# VS1005BOB-Pico-LCD_2024-02-10.net
KiCad netlist of a schematic drawn in Altium Designer
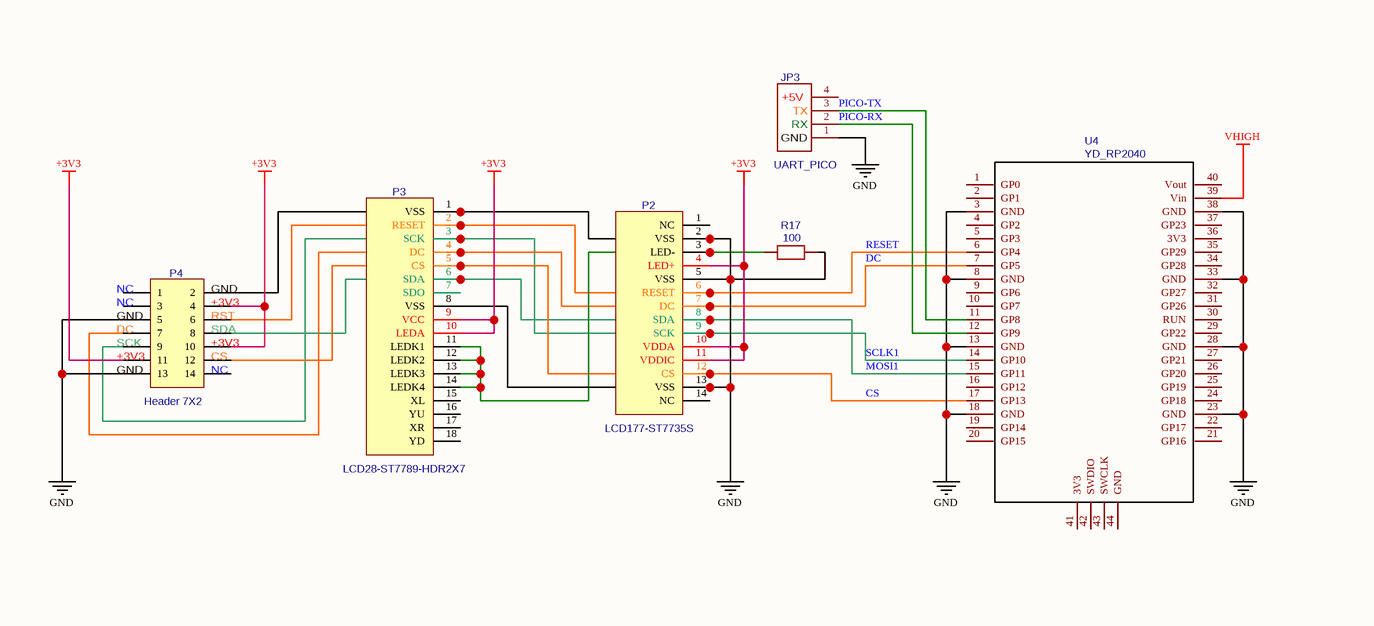
[diagram p0: VS1005BOB-Pico-LCD_2024-02-10.schdoc, left]
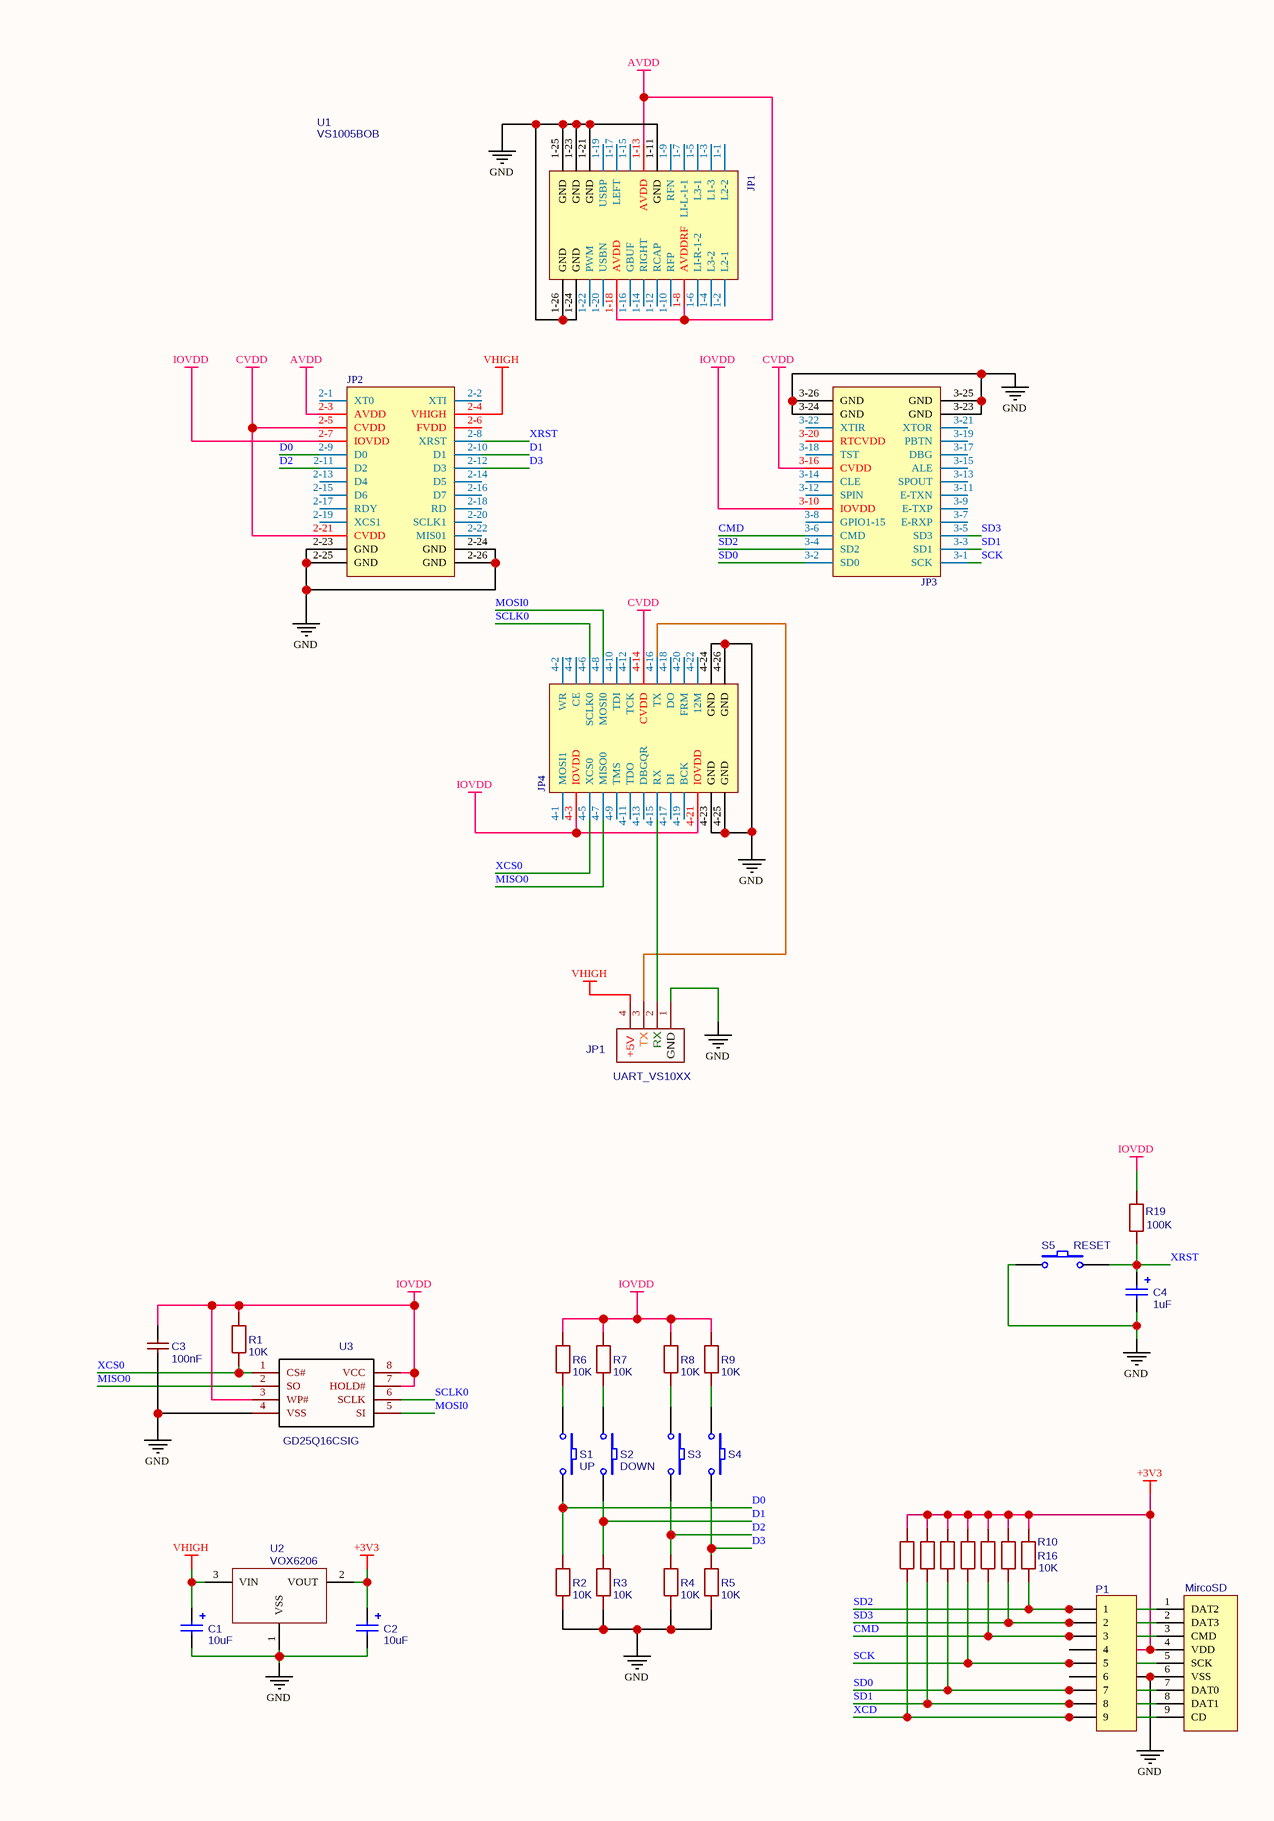
[diagram p1: VS1005BOB-Pico-LCD_2024-02-10.schdoc, right]

(export (version "E")
  (design (tool "Eeschema 10.0.6"))
  (components
    (comp (ref "C1")
      (value "10uF")
      (fields (field (name "PUBLISHER") "Altium Limited") (field (name "CONTRIBUTOR") "kmok163"))
      (libsource (lib "altium-import") (part "root_0_10uF_"))
    )
    (comp (ref "C2")
      (value "10uF")
      (fields (field (name "PUBLISHER") "Altium Limited") (field (name "CONTRIBUTOR") "kmok163"))
      (libsource (lib "altium-import") (part "root_0_10uF_"))
    )
    (comp (ref "C3")
      (value "100nF")
      (fields
        (field (name "MANUFACTURER PART") "CC0805KRX7R9BB104")
        (field (name "MANUFACTURER") "YAGEO")
        (field (name "CONTRIBUTOR") "fen-1")
      )
      (libsource (lib "altium-import") (part "root_3_100nF_"))
    )
    (comp (ref "C4")
      (value "1uF")
      (fields (field (name "PUBLISHER") "Altium Limited") (field (name "CONTRIBUTOR") "kmok163"))
      (libsource (lib "altium-import") (part "root_0_1uF_"))
    )
    (comp (ref "JP1")
      (value "UART_VS10XX")
      (description "Header 4")
      (fields (field (name "CONTRIBUTOR") "SparkFun"))
      (libsource (lib "altium-import") (part "root_1_UART_VS10XX_"))
    )
    (comp (ref "JP3")
      (value "UART_PICO")
      (description "Header 4")
      (fields (field (name "CONTRIBUTOR") "SparkFun"))
      (libsource (lib "altium-import") (part "root_0_UART_PICO_"))
    )
    (comp (ref "P1")
      (value "Header 9")
      (fields (field (name "PUBLISHER") "Altium Limited") (field (name "CONTRIBUTOR") "kmok163"))
      (libsource (lib "altium-import") (part "root_0_Header 9_"))
    )
    (comp (ref "P2")
      (value "LCD177-ST7735S")
      (fields (field (name "PUBLISHER") "Altium Limited") (field (name "CONTRIBUTOR") "kmok163"))
      (libsource (lib "altium-import") (part "root_0_LCD177-ST7735S_"))
    )
    (comp (ref "P3")
      (value "LCD28-ST7789-HDR2X7")
      (fields (field (name "PUBLISHER") "Altium Limited") (field (name "CONTRIBUTOR") "kmok163"))
      (libsource (lib "altium-import") (part "root_0_LCD28-ST7789-HDR2X7_"))
    )
    (comp (ref "P4")
      (value "Header 7X2")
      (fields (field (name "PUBLISHER") "Altium Limited") (field (name "CONTRIBUTOR") "lingtian"))
      (libsource (lib "altium-import") (part "root_0_Header 7X2_"))
    )
    (comp (ref "P6")
      (value "MircoSD")
      (fields (field (name "PUBLISHER") "Altium Limited") (field (name "CONTRIBUTOR") "kmok163"))
      (libsource (lib "altium-import") (part "root_0_MircoSD_"))
    )
    (comp (ref "R1")
      (value "10K")
      (fields (field (name "CONTRIBUTOR") "EDAUSER001"))
      (libsource (lib "altium-import") (part "root_1_10K_"))
    )
    (comp (ref "R2")
      (value "10K")
      (fields (field (name "CONTRIBUTOR") "EDAUSER001"))
      (libsource (lib "altium-import") (part "root_1_10K_"))
    )
    (comp (ref "R3")
      (value "10K")
      (fields (field (name "CONTRIBUTOR") "EDAUSER001"))
      (libsource (lib "altium-import") (part "root_1_10K_"))
    )
    (comp (ref "R4")
      (value "10K")
      (fields (field (name "CONTRIBUTOR") "EDAUSER001"))
      (libsource (lib "altium-import") (part "root_1_10K_"))
    )
    (comp (ref "R5")
      (value "10K")
      (fields (field (name "CONTRIBUTOR") "EDAUSER001"))
      (libsource (lib "altium-import") (part "root_1_10K_"))
    )
    (comp (ref "R6")
      (value "10K")
      (fields (field (name "CONTRIBUTOR") "EDAUSER001"))
      (libsource (lib "altium-import") (part "root_1_10K_"))
    )
    (comp (ref "R7")
      (value "10K")
      (fields (field (name "CONTRIBUTOR") "EDAUSER001"))
      (libsource (lib "altium-import") (part "root_1_10K_"))
    )
    (comp (ref "R8")
      (value "10K")
      (fields (field (name "CONTRIBUTOR") "EDAUSER001"))
      (libsource (lib "altium-import") (part "root_1_10K_"))
    )
    (comp (ref "R9")
      (value "10K")
      (fields (field (name "CONTRIBUTOR") "EDAUSER001"))
      (libsource (lib "altium-import") (part "root_1_10K_"))
    )
    (comp (ref "R10")
      (value "10K")
      (fields (field (name "CONTRIBUTOR") "EDAUSER001"))
      (libsource (lib "altium-import") (part "root_1_10K_"))
    )
    (comp (ref "R11")
      (value "10K")
      (fields (field (name "CONTRIBUTOR") "EDAUSER001"))
      (libsource (lib "altium-import") (part "root_1_10K_"))
    )
    (comp (ref "R12")
      (value "10K")
      (fields (field (name "CONTRIBUTOR") "EDAUSER001"))
      (libsource (lib "altium-import") (part "root_1_10K_"))
    )
    (comp (ref "R13")
      (value "10K")
      (fields (field (name "CONTRIBUTOR") "EDAUSER001"))
      (libsource (lib "altium-import") (part "root_1_10K_"))
    )
    (comp (ref "R14")
      (value "10K")
      (fields (field (name "CONTRIBUTOR") "EDAUSER001"))
      (libsource (lib "altium-import") (part "root_1_10K_"))
    )
    (comp (ref "R15")
      (value "10K")
      (fields (field (name "CONTRIBUTOR") "EDAUSER001"))
      (libsource (lib "altium-import") (part "root_1_10K_"))
    )
    (comp (ref "R16")
      (value "10K")
      (fields (field (name "CONTRIBUTOR") "EDAUSER001"))
      (libsource (lib "altium-import") (part "root_1_10K_"))
    )
    (comp (ref "R17")
      (value "100")
      (fields (field (name "CONTRIBUTOR") "EDAUSER001"))
      (libsource (lib "altium-import") (part "root_0_100_"))
    )
    (comp (ref "R19")
      (value "100K")
      (fields (field (name "CONTRIBUTOR") "EDAUSER001"))
      (libsource (lib "altium-import") (part "root_1_100K_"))
    )
    (comp (ref "S1")
      (value "UP")
      (fields (field (name "PUBLISHER") "Altium Limited") (field (name "CONTRIBUTOR") "kmok163"))
      (libsource (lib "altium-import") (part "root_3_UP_"))
    )
    (comp (ref "S2")
      (value "DOWN")
      (fields (field (name "PUBLISHER") "Altium Limited") (field (name "CONTRIBUTOR") "kmok163"))
      (libsource (lib "altium-import") (part "root_3_DOWN_"))
    )
    (comp (ref "S3")
      (value "D2")
      (fields (field (name "PUBLISHER") "Altium Limited") (field (name "CONTRIBUTOR") "kmok163"))
      (libsource (lib "altium-import") (part "root_3_D2_"))
    )
    (comp (ref "S4")
      (value "D3")
      (fields (field (name "PUBLISHER") "Altium Limited") (field (name "CONTRIBUTOR") "kmok163"))
      (libsource (lib "altium-import") (part "root_3_D3_"))
    )
    (comp (ref "S5")
      (value "RESET")
      (fields (field (name "PUBLISHER") "Altium Limited") (field (name "CONTRIBUTOR") "kmok163"))
      (libsource (lib "altium-import") (part "root_0_RESET_"))
    )
    (comp (ref "U1")
      (value "VS1005BOB")
      (fields (field (name "MANUFACTURER") "VLSI Solution Oy") (field (name "CONTRIBUTOR") "kmok163"))
      (libsource (lib "altium-import") (part "root_0_VS1005BOB_"))
    )
    (comp (ref "U2")
      (value "VOX6206")
      (fields (field (name "PUBLISHER") "Altium Limited") (field (name "CONTRIBUTOR") "kmok163"))
      (libsource (lib "altium-import") (part "root_0_VOX6206_"))
    )
    (comp (ref "U3")
      (value "GD25Q16CSIG")
      (fields (field (name "MANUFACTURER") "GigaDevice(兆易创新)"))
      (libsource (lib "altium-import") (part "root_0_GD25Q16CSIG_"))
    )
    (comp (ref "U4")
      (value "YD_RP2040")
      (fields (field (name "CONTRIBUTOR") "armxu"))
      (libsource (lib "altium-import") (part "root_0_YD_RP2040_"))
    )
  )
  (nets
    (net (code "1") (name "+3V3") (class "Default")
      (node (ref "C2") (pin "1") (pinfunction "1_1") (pintype "passive"))
      (node (ref "P1") (pin "4") (pinfunction "4_4") (pintype "passive"))
      (node (ref "P2") (pin "10") (pinfunction "VDDA_10") (pintype "passive"))
      (node (ref "P2") (pin "11") (pinfunction "VDDIC_11") (pintype "passive"))
      (node (ref "P2") (pin "4") (pinfunction "LED+_4") (pintype "passive"))
      (node (ref "P3") (pin "10") (pinfunction "LEDA_10") (pintype "passive"))
      (node (ref "P3") (pin "9") (pinfunction "VCC_9") (pintype "passive"))
      (node (ref "P4") (pin "10") (pinfunction "10_10") (pintype "passive"))
      (node (ref "P4") (pin "11") (pinfunction "11_11") (pintype "passive"))
      (node (ref "P4") (pin "4") (pinfunction "4_4") (pintype "passive"))
      (node (ref "P6") (pin "4") (pinfunction "VDD_4") (pintype "passive"))
      (node (ref "R10") (pin "2") (pinfunction "2_2") (pintype "passive"))
      (node (ref "R11") (pin "2") (pinfunction "2_2") (pintype "passive"))
      (node (ref "R12") (pin "2") (pinfunction "2_2") (pintype "passive"))
      (node (ref "R13") (pin "2") (pinfunction "2_2") (pintype "passive"))
      (node (ref "R14") (pin "2") (pinfunction "2_2") (pintype "passive"))
      (node (ref "R15") (pin "2") (pinfunction "2_2") (pintype "passive"))
      (node (ref "R16") (pin "2") (pinfunction "2_2") (pintype "passive"))
      (node (ref "U2") (pin "2") (pinfunction "VOUT_2") (pintype "passive"))
    )
    (net (code "2") (name "/CMD") (class "Default")
      (node (ref "P1") (pin "3") (pinfunction "3_3") (pintype "passive"))
      (node (ref "P6") (pin "3") (pinfunction "CMD_3") (pintype "passive"))
      (node (ref "R14") (pin "1") (pinfunction "1_1") (pintype "passive"))
      (node (ref "U1") (pin "3-6") (pinfunction "CMD_3-6") (pintype "passive"))
    )
    (net (code "3") (name "/CS") (class "Default")
      (node (ref "P2") (pin "12") (pinfunction "CS_12") (pintype "passive"))
      (node (ref "P3") (pin "5") (pinfunction "CS_5") (pintype "passive"))
      (node (ref "P4") (pin "12") (pinfunction "12_12") (pintype "passive"))
      (node (ref "U4") (pin "17") (pinfunction "GP13_17") (pintype "passive"))
    )
    (net (code "4") (name "/D0") (class "Default")
      (node (ref "R2") (pin "2") (pinfunction "2_2") (pintype "passive"))
      (node (ref "S1") (pin "2") (pinfunction "2_2") (pintype "passive"))
      (node (ref "U1") (pin "2-9") (pinfunction "D0_2-9") (pintype "passive"))
    )
    (net (code "5") (name "/D1") (class "Default")
      (node (ref "R3") (pin "2") (pinfunction "2_2") (pintype "passive"))
      (node (ref "S2") (pin "2") (pinfunction "2_2") (pintype "passive"))
      (node (ref "U1") (pin "2-10") (pinfunction "D1_2-10") (pintype "passive"))
    )
    (net (code "6") (name "/D2") (class "Default")
      (node (ref "R4") (pin "2") (pinfunction "2_2") (pintype "passive"))
      (node (ref "S3") (pin "2") (pinfunction "2_2") (pintype "passive"))
      (node (ref "U1") (pin "2-11") (pinfunction "D2_2-11") (pintype "passive"))
    )
    (net (code "7") (name "/D3") (class "Default")
      (node (ref "R5") (pin "2") (pinfunction "2_2") (pintype "passive"))
      (node (ref "S4") (pin "2") (pinfunction "2_2") (pintype "passive"))
      (node (ref "U1") (pin "2-12") (pinfunction "D3_2-12") (pintype "passive"))
    )
    (net (code "8") (name "/DC") (class "Default")
      (node (ref "P2") (pin "7") (pinfunction "DC_7") (pintype "passive"))
      (node (ref "P3") (pin "4") (pinfunction "DC_4") (pintype "passive"))
      (node (ref "P4") (pin "7") (pinfunction "7_7") (pintype "passive"))
      (node (ref "U4") (pin "7") (pinfunction "GP5_7") (pintype "passive"))
    )
    (net (code "9") (name "/MISO0") (class "Default")
      (node (ref "U1") (pin "4-7") (pinfunction "MISO0_4-7") (pintype "passive"))
      (node (ref "U3") (pin "2") (pinfunction "SO_2") (pintype "passive"))
    )
    (net (code "10") (name "/MOSI0") (class "Default")
      (node (ref "U1") (pin "4-8") (pinfunction "MOSI0_4-8") (pintype "passive"))
      (node (ref "U3") (pin "5") (pinfunction "SI_5") (pintype "passive"))
    )
    (net (code "11") (name "/MOSI1") (class "Default")
      (node (ref "P2") (pin "8") (pinfunction "SDA_8") (pintype "passive"))
      (node (ref "P3") (pin "6") (pinfunction "SDA_6") (pintype "passive"))
      (node (ref "P4") (pin "8") (pinfunction "8_8") (pintype "passive"))
      (node (ref "U4") (pin "15") (pinfunction "GP11_15") (pintype "passive"))
    )
    (net (code "12") (name "/PICO-RX") (class "Default")
      (node (ref "JP3") (pin "2") (pinfunction "2_2") (pintype "passive"))
      (node (ref "U4") (pin "12") (pinfunction "GP9_12") (pintype "passive"))
    )
    (net (code "13") (name "/PICO-TX") (class "Default")
      (node (ref "JP3") (pin "3") (pinfunction "3_3") (pintype "passive"))
      (node (ref "U4") (pin "11") (pinfunction "GP8_11") (pintype "passive"))
    )
    (net (code "14") (name "/RESET") (class "Default")
      (node (ref "P2") (pin "6") (pinfunction "RESET_6") (pintype "passive"))
      (node (ref "P3") (pin "2") (pinfunction "RESET_2") (pintype "passive"))
      (node (ref "P4") (pin "6") (pinfunction "6_6") (pintype "passive"))
      (node (ref "U4") (pin "6") (pinfunction "GP4_6") (pintype "passive"))
    )
    (net (code "15") (name "/SCK") (class "Default")
      (node (ref "P1") (pin "5") (pinfunction "5_5") (pintype "passive"))
      (node (ref "P6") (pin "5") (pinfunction "SCK_5") (pintype "passive"))
      (node (ref "R13") (pin "1") (pinfunction "1_1") (pintype "passive"))
      (node (ref "U1") (pin "3-1") (pinfunction "SCK_3-1") (pintype "passive"))
    )
    (net (code "16") (name "/SCLK0") (class "Default")
      (node (ref "U1") (pin "4-6") (pinfunction "SCLK0_4-6") (pintype "passive"))
      (node (ref "U3") (pin "6") (pinfunction "SCLK_6") (pintype "passive"))
    )
    (net (code "17") (name "/SCLK1") (class "Default")
      (node (ref "P2") (pin "9") (pinfunction "SCK_9") (pintype "passive"))
      (node (ref "P3") (pin "3") (pinfunction "SCK_3") (pintype "passive"))
      (node (ref "P4") (pin "9") (pinfunction "9_9") (pintype "passive"))
      (node (ref "U4") (pin "14") (pinfunction "GP10_14") (pintype "passive"))
    )
    (net (code "18") (name "/SD0") (class "Default")
      (node (ref "P1") (pin "7") (pinfunction "7_7") (pintype "passive"))
      (node (ref "P6") (pin "7") (pinfunction "DAT0_7") (pintype "passive"))
      (node (ref "R12") (pin "1") (pinfunction "1_1") (pintype "passive"))
      (node (ref "U1") (pin "3-2") (pinfunction "SD0_3-2") (pintype "passive"))
    )
    (net (code "19") (name "/SD1") (class "Default")
      (node (ref "P1") (pin "8") (pinfunction "8_8") (pintype "passive"))
      (node (ref "P6") (pin "8") (pinfunction "DAT1_8") (pintype "passive"))
      (node (ref "R11") (pin "1") (pinfunction "1_1") (pintype "passive"))
      (node (ref "U1") (pin "3-3") (pinfunction "SD1_3-3") (pintype "passive"))
    )
    (net (code "20") (name "/SD2") (class "Default")
      (node (ref "P1") (pin "1") (pinfunction "1_1") (pintype "passive"))
      (node (ref "P6") (pin "1") (pinfunction "DAT2_1") (pintype "passive"))
      (node (ref "R16") (pin "1") (pinfunction "1_1") (pintype "passive"))
      (node (ref "U1") (pin "3-4") (pinfunction "SD2_3-4") (pintype "passive"))
    )
    (net (code "21") (name "/SD3") (class "Default")
      (node (ref "P1") (pin "2") (pinfunction "2_2") (pintype "passive"))
      (node (ref "P6") (pin "2") (pinfunction "DAT3_2") (pintype "passive"))
      (node (ref "R15") (pin "1") (pinfunction "1_1") (pintype "passive"))
      (node (ref "U1") (pin "3-5") (pinfunction "SD3_3-5") (pintype "passive"))
    )
    (net (code "22") (name "/XCD") (class "Default")
      (node (ref "P1") (pin "9") (pinfunction "9_9") (pintype "passive"))
      (node (ref "P6") (pin "9") (pinfunction "CD_9") (pintype "passive"))
      (node (ref "R10") (pin "1") (pinfunction "1_1") (pintype "passive"))
    )
    (net (code "23") (name "/XCS0") (class "Default")
      (node (ref "R1") (pin "1") (pinfunction "1_1") (pintype "passive"))
      (node (ref "U1") (pin "4-5") (pinfunction "XCS0_4-5") (pintype "passive"))
      (node (ref "U3") (pin "1") (pinfunction "CS#_1") (pintype "passive"))
    )
    (net (code "24") (name "/XRST") (class "Default")
      (node (ref "C4") (pin "1") (pinfunction "1_1") (pintype "passive"))
      (node (ref "R19") (pin "1") (pinfunction "1_1") (pintype "passive"))
      (node (ref "S5") (pin "2") (pinfunction "2_2") (pintype "passive"))
      (node (ref "U1") (pin "2-8") (pinfunction "XRST_2-8") (pintype "passive"))
    )
    (net (code "25") (name "AVDD") (class "Default")
      (node (ref "U1") (pin "1-13") (pinfunction "AVDD_1-13") (pintype "passive"))
      (node (ref "U1") (pin "1-18") (pinfunction "AVDD_1-18") (pintype "passive"))
      (node (ref "U1") (pin "1-8") (pinfunction "AVDDRF_1-8") (pintype "passive"))
      (node (ref "U1") (pin "2-3") (pinfunction "AVDD_2-3") (pintype "passive"))
    )
    (net (code "26") (name "CVDD") (class "Default")
      (node (ref "U1") (pin "2-21") (pinfunction "CVDD_2-21") (pintype "passive"))
      (node (ref "U1") (pin "2-5") (pinfunction "CVDD_2-5") (pintype "passive"))
      (node (ref "U1") (pin "3-16") (pinfunction "CVDD_3-16") (pintype "passive"))
      (node (ref "U1") (pin "4-14") (pinfunction "CVDD_4-14") (pintype "passive"))
    )
    (net (code "27") (name "GND") (class "Default")
      (node (ref "C1") (pin "2") (pinfunction "2_2") (pintype "passive"))
      (node (ref "C2") (pin "2") (pinfunction "2_2") (pintype "passive"))
      (node (ref "C3") (pin "2") (pinfunction "2_2") (pintype "passive"))
      (node (ref "C4") (pin "2") (pinfunction "2_2") (pintype "passive"))
      (node (ref "JP1") (pin "1") (pinfunction "1_1") (pintype "passive"))
      (node (ref "JP3") (pin "1") (pinfunction "1_1") (pintype "passive"))
      (node (ref "P1") (pin "6") (pinfunction "6_6") (pintype "passive"))
      (node (ref "P2") (pin "13") (pinfunction "VSS_13") (pintype "passive"))
      (node (ref "P2") (pin "2") (pinfunction "VSS_2") (pintype "passive"))
      (node (ref "P2") (pin "5") (pinfunction "VSS_5") (pintype "passive"))
      (node (ref "P3") (pin "1") (pinfunction "VSS_1") (pintype "passive"))
      (node (ref "P3") (pin "8") (pinfunction "VSS_8") (pintype "passive"))
      (node (ref "P4") (pin "13") (pinfunction "13_13") (pintype "passive"))
      (node (ref "P4") (pin "2") (pinfunction "2_2") (pintype "passive"))
      (node (ref "P4") (pin "5") (pinfunction "5_5") (pintype "passive"))
      (node (ref "P6") (pin "6") (pinfunction "VSS_6") (pintype "passive"))
      (node (ref "R17") (pin "1") (pinfunction "1_1") (pintype "passive"))
      (node (ref "R2") (pin "1") (pinfunction "1_1") (pintype "passive"))
      (node (ref "R3") (pin "1") (pinfunction "1_1") (pintype "passive"))
      (node (ref "R4") (pin "1") (pinfunction "1_1") (pintype "passive"))
      (node (ref "R5") (pin "1") (pinfunction "1_1") (pintype "passive"))
      (node (ref "S5") (pin "1") (pinfunction "1_1") (pintype "passive"))
      (node (ref "U1") (pin "1-11") (pinfunction "GND_1-11") (pintype "passive"))
      (node (ref "U1") (pin "1-21") (pinfunction "GND_1-21") (pintype "passive"))
      (node (ref "U1") (pin "1-23") (pinfunction "GND_1-23") (pintype "passive"))
      (node (ref "U1") (pin "1-24") (pinfunction "GND_1-24") (pintype "passive"))
      (node (ref "U1") (pin "1-25") (pinfunction "GND_1-25") (pintype "passive"))
      (node (ref "U1") (pin "1-26") (pinfunction "GND_1-26") (pintype "passive"))
      (node (ref "U1") (pin "2-23") (pinfunction "GND_2-23") (pintype "passive"))
      (node (ref "U1") (pin "2-24") (pinfunction "GND_2-24") (pintype "passive"))
      (node (ref "U1") (pin "2-25") (pinfunction "GND_2-25") (pintype "passive"))
      (node (ref "U1") (pin "2-26") (pinfunction "GND_2-26") (pintype "passive"))
      (node (ref "U1") (pin "3-23") (pinfunction "GND_3-23") (pintype "passive"))
      (node (ref "U1") (pin "3-24") (pinfunction "GND_3-24") (pintype "passive"))
      (node (ref "U1") (pin "3-25") (pinfunction "GND_3-25") (pintype "passive"))
      (node (ref "U1") (pin "3-26") (pinfunction "GND_3-26") (pintype "passive"))
      (node (ref "U1") (pin "4-23") (pinfunction "GND_4-23") (pintype "passive"))
      (node (ref "U1") (pin "4-24") (pinfunction "GND_4-24") (pintype "passive"))
      (node (ref "U1") (pin "4-25") (pinfunction "GND_4-25") (pintype "passive"))
      (node (ref "U1") (pin "4-26") (pinfunction "GND_4-26") (pintype "passive"))
      (node (ref "U2") (pin "1") (pinfunction "VSS_1") (pintype "passive"))
      (node (ref "U3") (pin "4") (pinfunction "VSS_4") (pintype "passive"))
      (node (ref "U4") (pin "13") (pinfunction "GND_13") (pintype "passive"))
      (node (ref "U4") (pin "18") (pinfunction "GND_18") (pintype "passive"))
      (node (ref "U4") (pin "23") (pinfunction "GND_23") (pintype "passive"))
      (node (ref "U4") (pin "28") (pinfunction "GND_28") (pintype "passive"))
      (node (ref "U4") (pin "3") (pinfunction "GND_3") (pintype "passive"))
      (node (ref "U4") (pin "33") (pinfunction "GND_33") (pintype "passive"))
      (node (ref "U4") (pin "38") (pinfunction "GND_38") (pintype "passive"))
      (node (ref "U4") (pin "8") (pinfunction "GND_8") (pintype "passive"))
    )
    (net (code "28") (name "IOVDD") (class "Default")
      (node (ref "C3") (pin "1") (pinfunction "1_1") (pintype "passive"))
      (node (ref "R1") (pin "2") (pinfunction "2_2") (pintype "passive"))
      (node (ref "R19") (pin "2") (pinfunction "2_2") (pintype "passive"))
      (node (ref "R6") (pin "2") (pinfunction "2_2") (pintype "passive"))
      (node (ref "R7") (pin "2") (pinfunction "2_2") (pintype "passive"))
      (node (ref "R8") (pin "2") (pinfunction "2_2") (pintype "passive"))
      (node (ref "R9") (pin "2") (pinfunction "2_2") (pintype "passive"))
      (node (ref "U1") (pin "2-7") (pinfunction "IOVDD_2-7") (pintype "passive"))
      (node (ref "U1") (pin "3-10") (pinfunction "IOVDD_3-10") (pintype "passive"))
      (node (ref "U1") (pin "4-21") (pinfunction "IOVDD_4-21") (pintype "passive"))
      (node (ref "U1") (pin "4-3") (pinfunction "IOVDD_4-3") (pintype "passive"))
      (node (ref "U3") (pin "3") (pinfunction "WP#_3") (pintype "passive"))
      (node (ref "U3") (pin "7") (pinfunction "HOLD#_7") (pintype "passive"))
      (node (ref "U3") (pin "8") (pinfunction "VCC_8") (pintype "passive"))
    )
    (net (code "29") (name "Net-(P2-LED-)") (class "Default")
      (node (ref "P2") (pin "3") (pinfunction "LED-_3") (pintype "passive"))
      (node (ref "P3") (pin "11") (pinfunction "LEDK1_11") (pintype "passive"))
      (node (ref "P3") (pin "12") (pinfunction "LEDK2_12") (pintype "passive"))
      (node (ref "P3") (pin "13") (pinfunction "LEDK3_13") (pintype "passive"))
      (node (ref "P3") (pin "14") (pinfunction "LEDK4_14") (pintype "passive"))
      (node (ref "R17") (pin "2") (pinfunction "2_2") (pintype "passive"))
    )
    (net (code "30") (name "Net-(R6-Pad1)") (class "Default")
      (node (ref "R6") (pin "1") (pinfunction "1_1") (pintype "passive"))
      (node (ref "S1") (pin "1") (pinfunction "1_1") (pintype "passive"))
    )
    (net (code "31") (name "Net-(R7-Pad1)") (class "Default")
      (node (ref "R7") (pin "1") (pinfunction "1_1") (pintype "passive"))
      (node (ref "S2") (pin "1") (pinfunction "1_1") (pintype "passive"))
    )
    (net (code "32") (name "Net-(R8-Pad1)") (class "Default")
      (node (ref "R8") (pin "1") (pinfunction "1_1") (pintype "passive"))
      (node (ref "S3") (pin "1") (pinfunction "1_1") (pintype "passive"))
    )
    (net (code "33") (name "Net-(R9-Pad1)") (class "Default")
      (node (ref "R9") (pin "1") (pinfunction "1_1") (pintype "passive"))
      (node (ref "S4") (pin "1") (pinfunction "1_1") (pintype "passive"))
    )
    (net (code "34") (name "Net-(U1-RX)") (class "Default")
      (node (ref "JP1") (pin "2") (pinfunction "2_2") (pintype "passive"))
      (node (ref "U1") (pin "4-15") (pinfunction "RX_4-15") (pintype "passive"))
    )
    (net (code "35") (name "Net-(U1-TX)") (class "Default")
      (node (ref "JP1") (pin "3") (pinfunction "3_3") (pintype "passive"))
      (node (ref "U1") (pin "4-16") (pinfunction "TX_4-16") (pintype "passive"))
    )
    (net (code "36") (name "VHIGH") (class "Default")
      (node (ref "C1") (pin "1") (pinfunction "1_1") (pintype "passive"))
      (node (ref "JP1") (pin "4") (pinfunction "4_4") (pintype "passive"))
      (node (ref "U1") (pin "2-4") (pinfunction "VHIGH_2-4") (pintype "passive"))
      (node (ref "U2") (pin "3") (pinfunction "VIN_3") (pintype "passive"))
      (node (ref "U4") (pin "39") (pinfunction "Vin_39") (pintype "passive"))
    )
    (net (code "37") (name "unconnected-(JP3-Pad4)") (class "Default")
      (node (ref "JP3") (pin "4") (pinfunction "4_4") (pintype "passive"))
    )
    (net (code "38") (name "unconnected-(P2-NC-Pad1)") (class "Default")
      (node (ref "P2") (pin "1") (pinfunction "NC_1") (pintype "passive"))
    )
    (net (code "39") (name "unconnected-(P2-NC-Pad14)") (class "Default")
      (node (ref "P2") (pin "14") (pinfunction "NC_14") (pintype "passive"))
    )
    (net (code "40") (name "unconnected-(P3-SDO-Pad7)") (class "Default")
      (node (ref "P3") (pin "7") (pinfunction "SDO_7") (pintype "passive"))
    )
    (net (code "41") (name "unconnected-(P3-XL-Pad15)") (class "Default")
      (node (ref "P3") (pin "15") (pinfunction "XL_15") (pintype "passive"))
    )
    (net (code "42") (name "unconnected-(P3-XR-Pad17)") (class "Default")
      (node (ref "P3") (pin "17") (pinfunction "XR_17") (pintype "passive"))
    )
    (net (code "43") (name "unconnected-(P3-YD-Pad18)") (class "Default")
      (node (ref "P3") (pin "18") (pinfunction "YD_18") (pintype "passive"))
    )
    (net (code "44") (name "unconnected-(P3-YU-Pad16)") (class "Default")
      (node (ref "P3") (pin "16") (pinfunction "YU_16") (pintype "passive"))
    )
    (net (code "45") (name "unconnected-(P4-Pad1)") (class "Default")
      (node (ref "P4") (pin "1") (pinfunction "1_1") (pintype "passive"))
    )
    (net (code "46") (name "unconnected-(P4-Pad3)") (class "Default")
      (node (ref "P4") (pin "3") (pinfunction "3_3") (pintype "passive"))
    )
    (net (code "47") (name "unconnected-(P4-Pad14)") (class "Default")
      (node (ref "P4") (pin "14") (pinfunction "14_14") (pintype "passive"))
    )
    (net (code "48") (name "unconnected-(U1-12M-Pad4-22)") (class "Default")
      (node (ref "U1") (pin "4-22") (pinfunction "12M_4-22") (pintype "passive"))
    )
    (net (code "49") (name "unconnected-(U1-ALE-Pad3-15)") (class "Default")
      (node (ref "U1") (pin "3-15") (pinfunction "ALE_3-15") (pintype "passive"))
    )
    (net (code "50") (name "unconnected-(U1-BCK-Pad4-19)") (class "Default")
      (node (ref "U1") (pin "4-19") (pinfunction "BCK_4-19") (pintype "passive"))
    )
    (net (code "51") (name "unconnected-(U1-CE-Pad4-4)") (class "Default")
      (node (ref "U1") (pin "4-4") (pinfunction "CE_4-4") (pintype "passive"))
    )
    (net (code "52") (name "unconnected-(U1-CLE-Pad3-14)") (class "Default")
      (node (ref "U1") (pin "3-14") (pinfunction "CLE_3-14") (pintype "passive"))
    )
    (net (code "53") (name "unconnected-(U1-D4-Pad2-13)") (class "Default")
      (node (ref "U1") (pin "2-13") (pinfunction "D4_2-13") (pintype "passive"))
    )
    (net (code "54") (name "unconnected-(U1-D5-Pad2-14)") (class "Default")
      (node (ref "U1") (pin "2-14") (pinfunction "D5_2-14") (pintype "passive"))
    )
    (net (code "55") (name "unconnected-(U1-D6-Pad2-15)") (class "Default")
      (node (ref "U1") (pin "2-15") (pinfunction "D6_2-15") (pintype "passive"))
    )
    (net (code "56") (name "unconnected-(U1-D7-Pad2-16)") (class "Default")
      (node (ref "U1") (pin "2-16") (pinfunction "D7_2-16") (pintype "passive"))
    )
    (net (code "57") (name "unconnected-(U1-DBG-Pad3-17)") (class "Default")
      (node (ref "U1") (pin "3-17") (pinfunction "DBG_3-17") (pintype "passive"))
    )
    (net (code "58") (name "unconnected-(U1-DBGQR-Pad4-13)") (class "Default")
      (node (ref "U1") (pin "4-13") (pinfunction "DBGQR_4-13") (pintype "passive"))
    )
    (net (code "59") (name "unconnected-(U1-DI-Pad4-17)") (class "Default")
      (node (ref "U1") (pin "4-17") (pinfunction "DI_4-17") (pintype "passive"))
    )
    (net (code "60") (name "unconnected-(U1-DO-Pad4-18)") (class "Default")
      (node (ref "U1") (pin "4-18") (pinfunction "DO_4-18") (pintype "passive"))
    )
    (net (code "61") (name "unconnected-(U1-E-RXP-Pad3-7)") (class "Default")
      (node (ref "U1") (pin "3-7") (pinfunction "E-RXP_3-7") (pintype "passive"))
    )
    (net (code "62") (name "unconnected-(U1-E-TXN-Pad3-11)") (class "Default")
      (node (ref "U1") (pin "3-11") (pinfunction "E-TXN_3-11") (pintype "passive"))
    )
    (net (code "63") (name "unconnected-(U1-E-TXP-Pad3-9)") (class "Default")
      (node (ref "U1") (pin "3-9") (pinfunction "E-TXP_3-9") (pintype "passive"))
    )
    (net (code "64") (name "unconnected-(U1-FRM-Pad4-20)") (class "Default")
      (node (ref "U1") (pin "4-20") (pinfunction "FRM_4-20") (pintype "passive"))
    )
    (net (code "65") (name "unconnected-(U1-FVDD-Pad2-6)") (class "Default")
      (node (ref "U1") (pin "2-6") (pinfunction "FVDD_2-6") (pintype "passive"))
    )
    (net (code "66") (name "unconnected-(U1-GBUF-Pad1-16)") (class "Default")
      (node (ref "U1") (pin "1-16") (pinfunction "GBUF_1-16") (pintype "passive"))
    )
    (net (code "67") (name "unconnected-(U1-GPIO1-15-Pad3-8)") (class "Default")
      (node (ref "U1") (pin "3-8") (pinfunction "GPIO1-15_3-8") (pintype "passive"))
    )
    (net (code "68") (name "unconnected-(U1-L1-3-Pad1-3)") (class "Default")
      (node (ref "U1") (pin "1-3") (pinfunction "L1-3_1-3") (pintype "passive"))
    )
    (net (code "69") (name "unconnected-(U1-L2-1-Pad1-2)") (class "Default")
      (node (ref "U1") (pin "1-2") (pinfunction "L2-1_1-2") (pintype "passive"))
    )
    (net (code "70") (name "unconnected-(U1-L2-2-Pad1-1)") (class "Default")
      (node (ref "U1") (pin "1-1") (pinfunction "L2-2_1-1") (pintype "passive"))
    )
    (net (code "71") (name "unconnected-(U1-L3-1-Pad1-5)") (class "Default")
      (node (ref "U1") (pin "1-5") (pinfunction "L3-1_1-5") (pintype "passive"))
    )
    (net (code "72") (name "unconnected-(U1-L3-2-Pad1-4)") (class "Default")
      (node (ref "U1") (pin "1-4") (pinfunction "L3-2_1-4") (pintype "passive"))
    )
    (net (code "73") (name "unconnected-(U1-LEFT-Pad1-17)") (class "Default")
      (node (ref "U1") (pin "1-17") (pinfunction "LEFT_1-17") (pintype "passive"))
    )
    (net (code "74") (name "unconnected-(U1-LI-L-1-1-Pad1-7)") (class "Default")
      (node (ref "U1") (pin "1-7") (pinfunction "LI-L-1-1_1-7") (pintype "passive"))
    )
    (net (code "75") (name "unconnected-(U1-LI-R-1-2-Pad1-6)") (class "Default")
      (node (ref "U1") (pin "1-6") (pinfunction "LI-R-1-2_1-6") (pintype "passive"))
    )
    (net (code "76") (name "unconnected-(U1-MIS01-Pad2-22)") (class "Default")
      (node (ref "U1") (pin "2-22") (pinfunction "MIS01_2-22") (pintype "passive"))
    )
    (net (code "77") (name "unconnected-(U1-MOSI1-Pad4-1)") (class "Default")
      (node (ref "U1") (pin "4-1") (pinfunction "MOSI1_4-1") (pintype "passive"))
    )
    (net (code "78") (name "unconnected-(U1-PBTN-Pad3-19)") (class "Default")
      (node (ref "U1") (pin "3-19") (pinfunction "PBTN_3-19") (pintype "passive"))
    )
    (net (code "79") (name "unconnected-(U1-PWM-Pad1-22)") (class "Default")
      (node (ref "U1") (pin "1-22") (pinfunction "PWM_1-22") (pintype "passive"))
    )
    (net (code "80") (name "unconnected-(U1-Pad1-15)") (class "Default")
      (node (ref "U1") (pin "1-15") (pintype "passive"))
    )
    (net (code "81") (name "unconnected-(U1-RCAP-Pad1-12)") (class "Default")
      (node (ref "U1") (pin "1-12") (pinfunction "RCAP_1-12") (pintype "passive"))
    )
    (net (code "82") (name "unconnected-(U1-RD-Pad2-18)") (class "Default")
      (node (ref "U1") (pin "2-18") (pinfunction "RD_2-18") (pintype "passive"))
    )
    (net (code "83") (name "unconnected-(U1-RDY-Pad2-17)") (class "Default")
      (node (ref "U1") (pin "2-17") (pinfunction "RDY_2-17") (pintype "passive"))
    )
    (net (code "84") (name "unconnected-(U1-RFN-Pad1-9)") (class "Default")
      (node (ref "U1") (pin "1-9") (pinfunction "RFN_1-9") (pintype "passive"))
    )
    (net (code "85") (name "unconnected-(U1-RFP-Pad1-10)") (class "Default")
      (node (ref "U1") (pin "1-10") (pinfunction "RFP_1-10") (pintype "passive"))
    )
    (net (code "86") (name "unconnected-(U1-RIGHT-Pad1-14)") (class "Default")
      (node (ref "U1") (pin "1-14") (pinfunction "RIGHT_1-14") (pintype "passive"))
    )
    (net (code "87") (name "unconnected-(U1-RTCVDD-Pad3-20)") (class "Default")
      (node (ref "U1") (pin "3-20") (pinfunction "RTCVDD_3-20") (pintype "passive"))
    )
    (net (code "88") (name "unconnected-(U1-SCLK1-Pad2-20)") (class "Default")
      (node (ref "U1") (pin "2-20") (pinfunction "SCLK1_2-20") (pintype "passive"))
    )
    (net (code "89") (name "unconnected-(U1-SPIN-Pad3-12)") (class "Default")
      (node (ref "U1") (pin "3-12") (pinfunction "SPIN_3-12") (pintype "passive"))
    )
    (net (code "90") (name "unconnected-(U1-SPOUT-Pad3-13)") (class "Default")
      (node (ref "U1") (pin "3-13") (pinfunction "SPOUT_3-13") (pintype "passive"))
    )
    (net (code "91") (name "unconnected-(U1-TCK-Pad4-12)") (class "Default")
      (node (ref "U1") (pin "4-12") (pinfunction "TCK_4-12") (pintype "passive"))
    )
    (net (code "92") (name "unconnected-(U1-TDI-Pad4-10)") (class "Default")
      (node (ref "U1") (pin "4-10") (pinfunction "TDI_4-10") (pintype "passive"))
    )
    (net (code "93") (name "unconnected-(U1-TDO-Pad4-11)") (class "Default")
      (node (ref "U1") (pin "4-11") (pinfunction "TDO_4-11") (pintype "passive"))
    )
    (net (code "94") (name "unconnected-(U1-TMS-Pad4-9)") (class "Default")
      (node (ref "U1") (pin "4-9") (pinfunction "TMS_4-9") (pintype "passive"))
    )
    (net (code "95") (name "unconnected-(U1-TST-Pad3-18)") (class "Default")
      (node (ref "U1") (pin "3-18") (pinfunction "TST_3-18") (pintype "passive"))
    )
    (net (code "96") (name "unconnected-(U1-USBN-Pad1-20)") (class "Default")
      (node (ref "U1") (pin "1-20") (pinfunction "USBN_1-20") (pintype "passive"))
    )
    (net (code "97") (name "unconnected-(U1-USBP-Pad1-19)") (class "Default")
      (node (ref "U1") (pin "1-19") (pinfunction "USBP_1-19") (pintype "passive"))
    )
    (net (code "98") (name "unconnected-(U1-WR-Pad4-2)") (class "Default")
      (node (ref "U1") (pin "4-2") (pinfunction "WR_4-2") (pintype "passive"))
    )
    (net (code "99") (name "unconnected-(U1-XCS1-Pad2-19)") (class "Default")
      (node (ref "U1") (pin "2-19") (pinfunction "XCS1_2-19") (pintype "passive"))
    )
    (net (code "100") (name "unconnected-(U1-XT0-Pad2-1)") (class "Default")
      (node (ref "U1") (pin "2-1") (pinfunction "XT0_2-1") (pintype "passive"))
    )
    (net (code "101") (name "unconnected-(U1-XTI-Pad2-2)") (class "Default")
      (node (ref "U1") (pin "2-2") (pinfunction "XTI_2-2") (pintype "passive"))
    )
    (net (code "102") (name "unconnected-(U1-XTIR-Pad3-22)") (class "Default")
      (node (ref "U1") (pin "3-22") (pinfunction "XTIR_3-22") (pintype "passive"))
    )
    (net (code "103") (name "unconnected-(U1-XTOR-Pad3-21)") (class "Default")
      (node (ref "U1") (pin "3-21") (pinfunction "XTOR_3-21") (pintype "passive"))
    )
    (net (code "104") (name "unconnected-(U4-3V3-Pad36)") (class "Default")
      (node (ref "U4") (pin "36") (pinfunction "3V3_36") (pintype "passive"))
    )
    (net (code "105") (name "unconnected-(U4-3V3-Pad41)") (class "Default")
      (node (ref "U4") (pin "41") (pinfunction "3V3_41") (pintype "passive"))
    )
    (net (code "106") (name "unconnected-(U4-GND-Pad44)") (class "Default")
      (node (ref "U4") (pin "44") (pinfunction "GND_44") (pintype "passive"))
    )
    (net (code "107") (name "unconnected-(U4-GP0-Pad1)") (class "Default")
      (node (ref "U4") (pin "1") (pinfunction "GP0_1") (pintype "passive"))
    )
    (net (code "108") (name "unconnected-(U4-GP1-Pad2)") (class "Default")
      (node (ref "U4") (pin "2") (pinfunction "GP1_2") (pintype "passive"))
    )
    (net (code "109") (name "unconnected-(U4-GP2-Pad4)") (class "Default")
      (node (ref "U4") (pin "4") (pinfunction "GP2_4") (pintype "passive"))
    )
    (net (code "110") (name "unconnected-(U4-GP3-Pad5)") (class "Default")
      (node (ref "U4") (pin "5") (pinfunction "GP3_5") (pintype "passive"))
    )
    (net (code "111") (name "unconnected-(U4-GP6-Pad9)") (class "Default")
      (node (ref "U4") (pin "9") (pinfunction "GP6_9") (pintype "passive"))
    )
    (net (code "112") (name "unconnected-(U4-GP7-Pad10)") (class "Default")
      (node (ref "U4") (pin "10") (pinfunction "GP7_10") (pintype "passive"))
    )
    (net (code "113") (name "unconnected-(U4-GP12-Pad16)") (class "Default")
      (node (ref "U4") (pin "16") (pinfunction "GP12_16") (pintype "passive"))
    )
    (net (code "114") (name "unconnected-(U4-GP14-Pad19)") (class "Default")
      (node (ref "U4") (pin "19") (pinfunction "GP14_19") (pintype "passive"))
    )
    (net (code "115") (name "unconnected-(U4-GP15-Pad20)") (class "Default")
      (node (ref "U4") (pin "20") (pinfunction "GP15_20") (pintype "passive"))
    )
    (net (code "116") (name "unconnected-(U4-GP16-Pad21)") (class "Default")
      (node (ref "U4") (pin "21") (pinfunction "GP16_21") (pintype "passive"))
    )
    (net (code "117") (name "unconnected-(U4-GP17-Pad22)") (class "Default")
      (node (ref "U4") (pin "22") (pinfunction "GP17_22") (pintype "passive"))
    )
    (net (code "118") (name "unconnected-(U4-GP18-Pad24)") (class "Default")
      (node (ref "U4") (pin "24") (pinfunction "GP18_24") (pintype "passive"))
    )
    (net (code "119") (name "unconnected-(U4-GP19-Pad25)") (class "Default")
      (node (ref "U4") (pin "25") (pinfunction "GP19_25") (pintype "passive"))
    )
    (net (code "120") (name "unconnected-(U4-GP20-Pad26)") (class "Default")
      (node (ref "U4") (pin "26") (pinfunction "GP20_26") (pintype "passive"))
    )
    (net (code "121") (name "unconnected-(U4-GP21-Pad27)") (class "Default")
      (node (ref "U4") (pin "27") (pinfunction "GP21_27") (pintype "passive"))
    )
    (net (code "122") (name "unconnected-(U4-GP22-Pad29)") (class "Default")
      (node (ref "U4") (pin "29") (pinfunction "GP22_29") (pintype "passive"))
    )
    (net (code "123") (name "unconnected-(U4-GP23-Pad37)") (class "Default")
      (node (ref "U4") (pin "37") (pinfunction "GP23_37") (pintype "passive"))
    )
    (net (code "124") (name "unconnected-(U4-GP26-Pad31)") (class "Default")
      (node (ref "U4") (pin "31") (pinfunction "GP26_31") (pintype "passive"))
    )
    (net (code "125") (name "unconnected-(U4-GP27-Pad32)") (class "Default")
      (node (ref "U4") (pin "32") (pinfunction "GP27_32") (pintype "passive"))
    )
    (net (code "126") (name "unconnected-(U4-GP28-Pad34)") (class "Default")
      (node (ref "U4") (pin "34") (pinfunction "GP28_34") (pintype "passive"))
    )
    (net (code "127") (name "unconnected-(U4-GP29-Pad35)") (class "Default")
      (node (ref "U4") (pin "35") (pinfunction "GP29_35") (pintype "passive"))
    )
    (net (code "128") (name "unconnected-(U4-RUN-Pad30)") (class "Default")
      (node (ref "U4") (pin "30") (pinfunction "RUN_30") (pintype "passive"))
    )
    (net (code "129") (name "unconnected-(U4-SWCLK-Pad43)") (class "Default")
      (node (ref "U4") (pin "43") (pinfunction "SWCLK_43") (pintype "passive"))
    )
    (net (code "130") (name "unconnected-(U4-SWDIO-Pad42)") (class "Default")
      (node (ref "U4") (pin "42") (pinfunction "SWDIO_42") (pintype "passive"))
    )
    (net (code "131") (name "unconnected-(U4-Vout-Pad40)") (class "Default")
      (node (ref "U4") (pin "40") (pinfunction "Vout_40") (pintype "passive"))
    )
  )
)
